# CW308T_S6LX9_Connector.net
KiCad netlist of a schematic drawn in Altium Designer
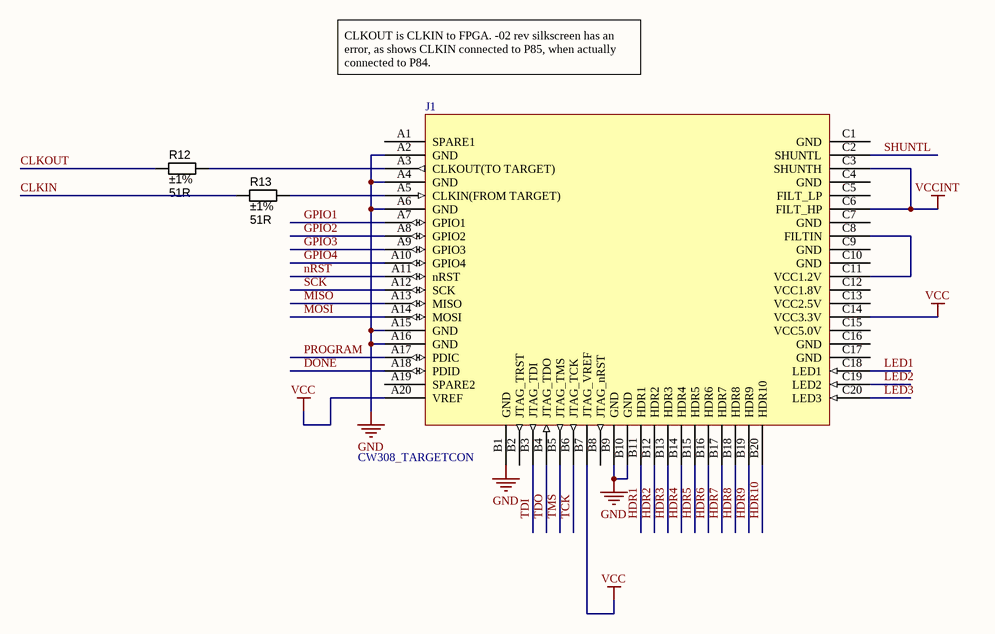
[diagram p0: CW308T_S6LX9_Connector.SchDoc]

(export (version "E")
  (design (tool "Eeschema 10.0.6"))
  (components
    (comp (ref "J1")
      (value "CW308_TARGETCON")
      (footprint "ChipWhisperer_AltiumLib:CW308_TBOARD_CONN")
      (description "CW308 \"Standard\" Target Board Connector")
      (libsource (lib "ChipWhisperer_AltiumLib") (part "CW308_TBOARD"))
    )
    (comp (ref "R12")
      (value "51R")
      (footprint "RESC1608X55N")
      (description "Resistor SMD chip 51 Ohm 0.1W 1% 0603")
      (fields (field (name "TOLERANCE") "±1%") (field (name "Comment") "Thick Film"))
      (libsource (lib "PBL - Resistors") (part "RES_51R_0603_1%"))
    )
    (comp (ref "R13")
      (value "51R")
      (footprint "RESC1608X55N")
      (description "Resistor SMD chip 51 Ohm 0.1W 1% 0603")
      (fields (field (name "TOLERANCE") "±1%") (field (name "Comment") "Thick Film"))
      (libsource (lib "PBL - Resistors") (part "RES_51R_0603_1%"))
    )
  )
  (nets
    (net (code "1") (name "/CLKIN") (class "Default")
      (node (ref "R13") (pin "1") (pinfunction "1_1") (pintype "passive"))
    )
    (net (code "2") (name "/CLKOUT") (class "Default")
      (node (ref "R12") (pin "1") (pinfunction "1_1") (pintype "passive"))
    )
    (net (code "3") (name "/DONE") (class "Default")
      (node (ref "J1") (pin "A18") (pinfunction "PDID_A18") (pintype "bidirectional"))
    )
    (net (code "4") (name "/GPIO1") (class "Default")
      (node (ref "J1") (pin "A7") (pinfunction "GPIO1_A7") (pintype "bidirectional"))
    )
    (net (code "5") (name "/GPIO2") (class "Default")
      (node (ref "J1") (pin "A8") (pinfunction "GPIO2_A8") (pintype "bidirectional"))
    )
    (net (code "6") (name "/GPIO3") (class "Default")
      (node (ref "J1") (pin "A9") (pinfunction "GPIO3_A9") (pintype "bidirectional"))
    )
    (net (code "7") (name "/GPIO4") (class "Default")
      (node (ref "J1") (pin "A10") (pinfunction "GPIO4_A10") (pintype "bidirectional"))
    )
    (net (code "8") (name "/HDR1") (class "Default")
      (node (ref "J1") (pin "B11") (pinfunction "HDR1_B11") (pintype "passive"))
    )
    (net (code "9") (name "/HDR2") (class "Default")
      (node (ref "J1") (pin "B12") (pinfunction "HDR2_B12") (pintype "passive"))
    )
    (net (code "10") (name "/HDR3") (class "Default")
      (node (ref "J1") (pin "B13") (pinfunction "HDR3_B13") (pintype "passive"))
    )
    (net (code "11") (name "/HDR4") (class "Default")
      (node (ref "J1") (pin "B14") (pinfunction "HDR4_B14") (pintype "passive"))
    )
    (net (code "12") (name "/HDR5") (class "Default")
      (node (ref "J1") (pin "B15") (pinfunction "HDR5_B15") (pintype "passive"))
    )
    (net (code "13") (name "/HDR6") (class "Default")
      (node (ref "J1") (pin "B16") (pinfunction "HDR6_B16") (pintype "passive"))
    )
    (net (code "14") (name "/HDR7") (class "Default")
      (node (ref "J1") (pin "B17") (pinfunction "HDR7_B17") (pintype "passive"))
    )
    (net (code "15") (name "/HDR8") (class "Default")
      (node (ref "J1") (pin "B18") (pinfunction "HDR8_B18") (pintype "passive"))
    )
    (net (code "16") (name "/HDR9") (class "Default")
      (node (ref "J1") (pin "B19") (pinfunction "HDR9_B19") (pintype "passive"))
    )
    (net (code "17") (name "/HDR10") (class "Default")
      (node (ref "J1") (pin "B20") (pinfunction "HDR10_B20") (pintype "passive"))
    )
    (net (code "18") (name "/LED1") (class "Default")
      (node (ref "J1") (pin "C18") (pinfunction "LED1_C18") (pintype "input"))
    )
    (net (code "19") (name "/LED2") (class "Default")
      (node (ref "J1") (pin "C19") (pinfunction "LED2_C19") (pintype "input"))
    )
    (net (code "20") (name "/LED3") (class "Default")
      (node (ref "J1") (pin "C20") (pinfunction "LED3_C20") (pintype "input"))
    )
    (net (code "21") (name "/MISO") (class "Default")
      (node (ref "J1") (pin "A13") (pinfunction "MISO_A13") (pintype "bidirectional"))
    )
    (net (code "22") (name "/MOSI") (class "Default")
      (node (ref "J1") (pin "A14") (pinfunction "MOSI_A14") (pintype "bidirectional"))
    )
    (net (code "23") (name "/PROGRAM") (class "Default")
      (node (ref "J1") (pin "A17") (pinfunction "PDIC_A17") (pintype "bidirectional"))
    )
    (net (code "24") (name "/SCK") (class "Default")
      (node (ref "J1") (pin "A12") (pinfunction "SCK_A12") (pintype "bidirectional"))
    )
    (net (code "25") (name "/SHUNTL") (class "Default")
      (node (ref "J1") (pin "C2") (pinfunction "SHUNTL_C2") (pintype "passive"))
    )
    (net (code "26") (name "/TCK") (class "Default")
      (node (ref "J1") (pin "B6") (pinfunction "JTAG_TCK_B6") (pintype "output"))
    )
    (net (code "27") (name "/TDI") (class "Default")
      (node (ref "J1") (pin "B3") (pinfunction "JTAG_TDI_B3") (pintype "output"))
    )
    (net (code "28") (name "/TDO") (class "Default")
      (node (ref "J1") (pin "B4") (pinfunction "JTAG_TDO_B4") (pintype "input"))
    )
    (net (code "29") (name "/TMS") (class "Default")
      (node (ref "J1") (pin "B5") (pinfunction "JTAG_TMS_B5") (pintype "output"))
    )
    (net (code "30") (name "/nRST") (class "Default")
      (node (ref "J1") (pin "A11") (pinfunction "nRST_A11") (pintype "bidirectional"))
    )
    (net (code "31") (name "GND") (class "Default")
      (node (ref "J1") (pin "A15") (pinfunction "GND_A15") (pintype "passive"))
      (node (ref "J1") (pin "A16") (pinfunction "GND_A16") (pintype "passive"))
      (node (ref "J1") (pin "A2") (pinfunction "GND_A2") (pintype "passive"))
      (node (ref "J1") (pin "A4") (pinfunction "GND_A4") (pintype "passive"))
      (node (ref "J1") (pin "A6") (pinfunction "GND_A6") (pintype "power_in"))
      (node (ref "J1") (pin "B1") (pinfunction "GND_B1") (pintype "passive"))
      (node (ref "J1") (pin "B10") (pinfunction "GND_B10") (pintype "passive"))
      (node (ref "J1") (pin "B9") (pinfunction "GND_B9") (pintype "passive"))
    )
    (net (code "32") (name "Net-(J1-CLKIN(FROM_TARGET))") (class "Default")
      (node (ref "J1") (pin "A5") (pinfunction "CLKIN(FROM_TARGET)_A5") (pintype "input"))
      (node (ref "R13") (pin "2") (pinfunction "2_2") (pintype "passive"))
    )
    (net (code "33") (name "Net-(J1-CLKOUT(TO_TARGET))") (class "Default")
      (node (ref "J1") (pin "A3") (pinfunction "CLKOUT(TO_TARGET)_A3") (pintype "output"))
      (node (ref "R12") (pin "2") (pinfunction "2_2") (pintype "passive"))
    )
    (net (code "34") (name "Net-(J1-FILTIN)") (class "Default")
      (node (ref "J1") (pin "C11") (pinfunction "VCC1.2V_C11") (pintype "power_in"))
      (node (ref "J1") (pin "C8") (pinfunction "FILTIN_C8") (pintype "passive"))
    )
    (net (code "35") (name "VCC") (class "Default")
      (node (ref "J1") (pin "A20") (pinfunction "VREF_A20") (pintype "tri_state"))
      (node (ref "J1") (pin "B7") (pinfunction "JTAG_VREF_B7") (pintype "tri_state"))
      (node (ref "J1") (pin "C14") (pinfunction "VCC3.3V_C14") (pintype "power_in"))
    )
    (net (code "36") (name "VCCINT") (class "Default")
      (node (ref "J1") (pin "C3") (pinfunction "SHUNTH_C3") (pintype "passive"))
      (node (ref "J1") (pin "C6") (pinfunction "FILT_HP_C6") (pintype "passive"))
    )
    (net (code "37") (name "unconnected-(J1-FILT_LP-PadC5)") (class "Default")
      (node (ref "J1") (pin "C5") (pinfunction "FILT_LP_C5") (pintype "passive"))
    )
    (net (code "38") (name "unconnected-(J1-GND-PadC1)") (class "Default")
      (node (ref "J1") (pin "C1") (pinfunction "GND_C1") (pintype "power_in"))
    )
    (net (code "39") (name "unconnected-(J1-GND-PadC4)") (class "Default")
      (node (ref "J1") (pin "C4") (pinfunction "GND_C4") (pintype "power_in"))
    )
    (net (code "40") (name "unconnected-(J1-GND-PadC7)") (class "Default")
      (node (ref "J1") (pin "C7") (pinfunction "GND_C7") (pintype "power_in"))
    )
    (net (code "41") (name "unconnected-(J1-GND-PadC9)") (class "Default")
      (node (ref "J1") (pin "C9") (pinfunction "GND_C9") (pintype "power_in"))
    )
    (net (code "42") (name "unconnected-(J1-GND-PadC10)") (class "Default")
      (node (ref "J1") (pin "C10") (pinfunction "GND_C10") (pintype "power_in"))
    )
    (net (code "43") (name "unconnected-(J1-GND-PadC16)") (class "Default")
      (node (ref "J1") (pin "C16") (pinfunction "GND_C16") (pintype "power_in"))
    )
    (net (code "44") (name "unconnected-(J1-GND-PadC17)") (class "Default")
      (node (ref "J1") (pin "C17") (pinfunction "GND_C17") (pintype "power_in"))
    )
    (net (code "45") (name "unconnected-(J1-JTAG_TRST-PadB2)") (class "Default")
      (node (ref "J1") (pin "B2") (pinfunction "JTAG_TRST_B2") (pintype "output"))
    )
    (net (code "46") (name "unconnected-(J1-JTAG_nRST-PadB8)") (class "Default")
      (node (ref "J1") (pin "B8") (pinfunction "JTAG_nRST_B8") (pintype "output"))
    )
    (net (code "47") (name "unconnected-(J1-SPARE1-PadA1)") (class "Default")
      (node (ref "J1") (pin "A1") (pinfunction "SPARE1_A1") (pintype "passive"))
    )
    (net (code "48") (name "unconnected-(J1-SPARE2-PadA19)") (class "Default")
      (node (ref "J1") (pin "A19") (pinfunction "SPARE2_A19") (pintype "passive"))
    )
    (net (code "49") (name "unconnected-(J1-VCC1.8V-PadC12)") (class "Default")
      (node (ref "J1") (pin "C12") (pinfunction "VCC1.8V_C12") (pintype "power_in"))
    )
    (net (code "50") (name "unconnected-(J1-VCC2.5V-PadC13)") (class "Default")
      (node (ref "J1") (pin "C13") (pinfunction "VCC2.5V_C13") (pintype "power_in"))
    )
    (net (code "51") (name "unconnected-(J1-VCC5.0V-PadC15)") (class "Default")
      (node (ref "J1") (pin "C15") (pinfunction "VCC5.0V_C15") (pintype "power_in"))
    )
  )
)
